# PCB.net
KiCad netlist of a schematic drawn in Altium Designer
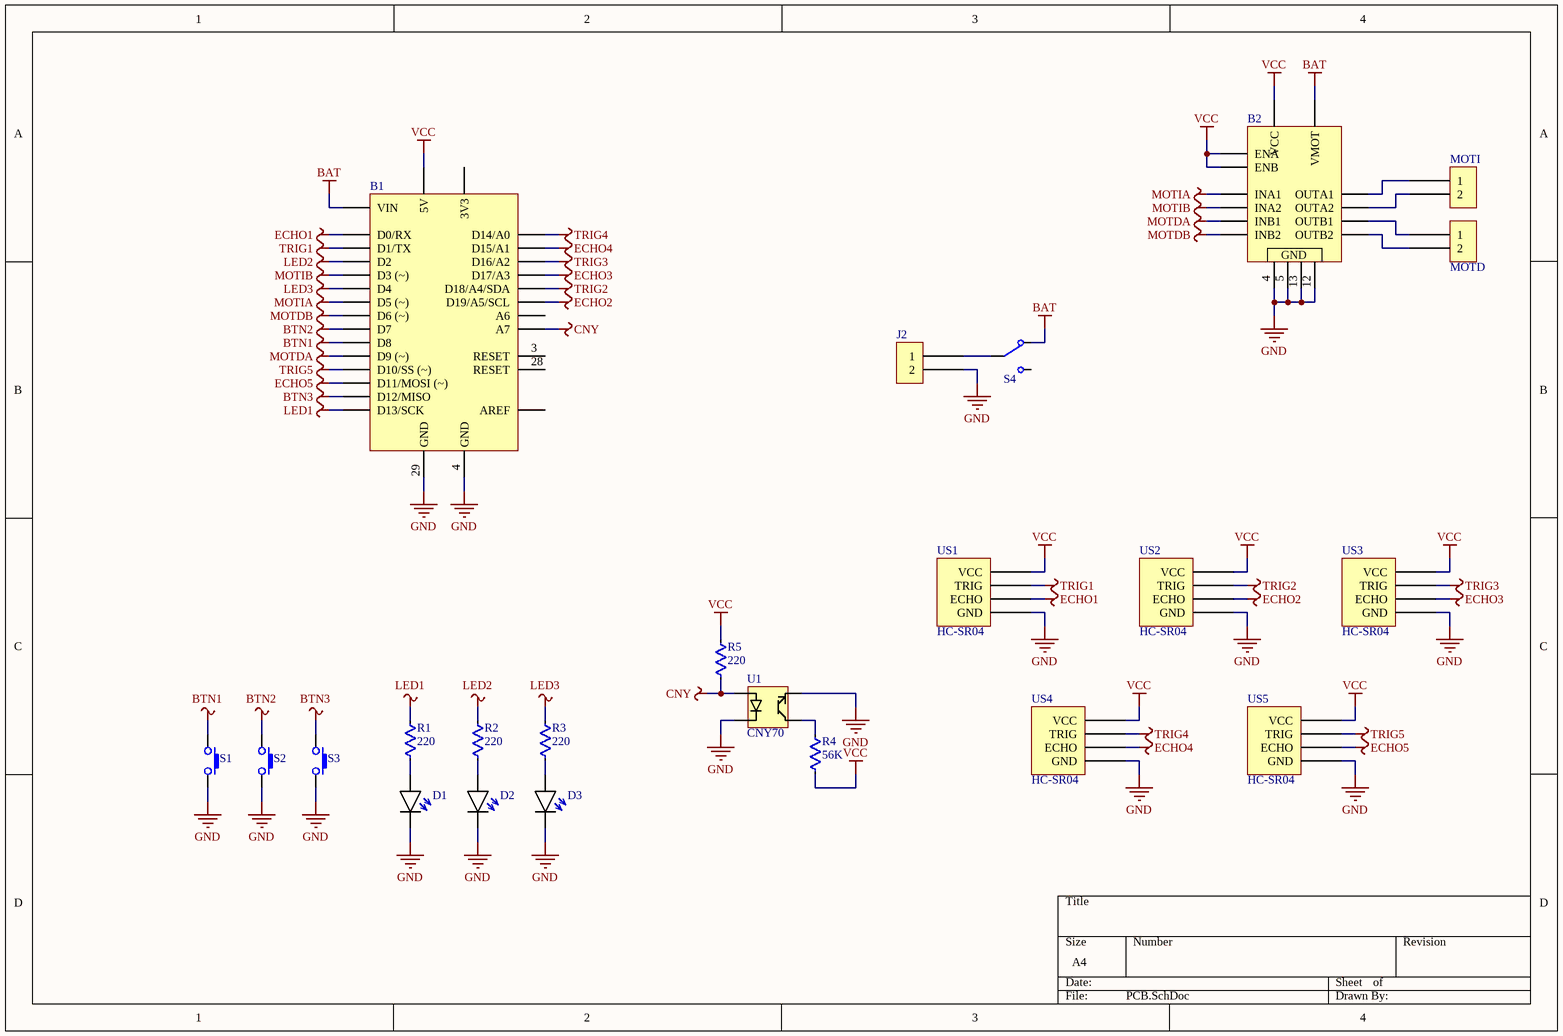
[diagram p0: PCB.SchDoc]

(export (version "E")
  (design (tool "Eeschema 10.0.6"))
  (components
    (comp (ref "B1")
      (value "ARDUINO NANO")
      (footprint "ARDUINO NANO")
      (fields (field (name "MANUFACTURER_PART_NUMBER") "Nano") (field (name "RS PART NUMBER") "6961667"))
      (libsource (lib "AltiumLibrary") (part "ARDUINO NANO"))
    )
    (comp (ref "B2") (value "L293D") (footprint "DIP16") (libsource (lib "AltiumLibrary") (part "L293D")))
    (comp (ref "D1") (value "LED") (footprint "LED-3MM-RED") (libsource (lib "AltiumLibrary") (part "LED")))
    (comp (ref "D2")
      (value "LED")
      (footprint "LED-3MM-YELLOW")
      (libsource (lib "AltiumLibrary") (part "LED"))
    )
    (comp (ref "D3") (value "LED") (footprint "LED-3MM-GREEN") (libsource (lib "AltiumLibrary") (part "LED")))
    (comp (ref "J2") (value "Header 1x2") (footprint "HEADER 1x2") (libsource (lib "") (part "Header 1x2_1")))
    (comp (ref "MOTD")
      (value "Header 1x2")
      (footprint "HEADER 1x2")
      (libsource (lib "AltiumLibrary") (part "Header 1x2"))
    )
    (comp (ref "MOTI")
      (value "Header 1x2")
      (footprint "HEADER 1x2")
      (libsource (lib "AltiumLibrary") (part "Header 1x2"))
    )
    (comp (ref "R1")
      (value "220")
      (footprint "RES VERTICAL")
      (fields (field (name "Comment") "RES"))
      (libsource (lib "AltiumLibrary") (part "RES"))
    )
    (comp (ref "R2")
      (value "220")
      (footprint "RES-Axial-400mil")
      (fields (field (name "Comment") "RES"))
      (libsource (lib "AltiumLibrary") (part "RES"))
    )
    (comp (ref "R3")
      (value "220")
      (footprint "RES-Axial-400mil")
      (fields (field (name "Comment") "RES"))
      (libsource (lib "AltiumLibrary") (part "RES"))
    )
    (comp (ref "R4")
      (value "56K")
      (footprint "RES-Axial-400mil")
      (fields (field (name "Comment") "RES"))
      (libsource (lib "AltiumLibrary") (part "RES"))
    )
    (comp (ref "R5")
      (value "220")
      (footprint "RES-Axial-400mil")
      (fields (field (name "Comment") "RES"))
      (libsource (lib "AltiumLibrary") (part "RES"))
    )
    (comp (ref "S1")
      (value "BUTTON")
      (footprint "TACT_SWITCH-SMALL-4PIN")
      (libsource (lib "AltiumLibrary") (part "BUTTON"))
    )
    (comp (ref "S2")
      (value "BUTTON")
      (footprint "TACT_SWITCH-SMALL-4PIN")
      (libsource (lib "AltiumLibrary") (part "BUTTON"))
    )
    (comp (ref "S3")
      (value "BUTTON")
      (footprint "TACT_SWITCH-SMALL-4PIN")
      (libsource (lib "AltiumLibrary") (part "BUTTON"))
    )
    (comp (ref "S4")
      (value "SLIDE-SWITCH")
      (footprint "SWITCH")
      (libsource (lib "AltiumLibrary") (part "SLIDE-SWITCH"))
    )
    (comp (ref "U1") (value "CNY70") (footprint "CNY70") (libsource (lib "AltiumLibrary") (part "CNY70")))
    (comp (ref "US1")
      (value "HC-SR04")
      (footprint "HC-SR04")
      (libsource (lib "AltiumLibrary") (part "HC-SR04"))
    )
    (comp (ref "US2")
      (value "HC-SR04")
      (footprint "HC-SR04")
      (libsource (lib "AltiumLibrary") (part "HC-SR04"))
    )
    (comp (ref "US3")
      (value "HC-SR04")
      (footprint "HC-SR04")
      (libsource (lib "AltiumLibrary") (part "HC-SR04"))
    )
    (comp (ref "US4")
      (value "HC-SR04")
      (footprint "HC-SR04")
      (libsource (lib "AltiumLibrary") (part "HC-SR04"))
    )
    (comp (ref "US5")
      (value "HC-SR04")
      (footprint "HC-SR04")
      (libsource (lib "AltiumLibrary") (part "HC-SR04"))
    )
  )
  (nets
    (net (code "1") (name "BAT") (class "Default")
      (node (ref "B1") (pin "30") (pinfunction "VIN_30") (pintype "passive"))
      (node (ref "B2") (pin "8") (pinfunction "VMOT_8") (pintype "passive"))
      (node (ref "S4") (pin "1") (pintype "power_in"))
    )
    (net (code "2") (name "BTN1") (class "Default")
      (node (ref "B1") (pin "11") (pinfunction "D8_11") (pintype "passive"))
      (node (ref "S1") (pin "1") (pintype "passive"))
    )
    (net (code "3") (name "BTN2") (class "Default")
      (node (ref "B1") (pin "10") (pinfunction "D7_10") (pintype "passive"))
      (node (ref "S2") (pin "1") (pintype "passive"))
    )
    (net (code "4") (name "BTN3") (class "Default")
      (node (ref "B1") (pin "15") (pinfunction "D12/MISO_15") (pintype "passive"))
      (node (ref "S3") (pin "1") (pintype "passive"))
    )
    (net (code "5") (name "CNY") (class "Default")
      (node (ref "B1") (pin "26") (pinfunction "A7_26") (pintype "passive"))
      (node (ref "R5") (pin "1") (pintype "passive"))
      (node (ref "U1") (pin "A") (pinfunction "A_A") (pintype "passive"))
    )
    (net (code "6") (name "ECHO1") (class "Default")
      (node (ref "B1") (pin "2") (pinfunction "D0/RX_2") (pintype "passive"))
      (node (ref "US1") (pin "3") (pinfunction "ECHO_3") (pintype "passive"))
    )
    (net (code "7") (name "ECHO2") (class "Default")
      (node (ref "B1") (pin "24") (pinfunction "D19/A5/SCL_24") (pintype "passive"))
      (node (ref "US2") (pin "3") (pinfunction "ECHO_3") (pintype "passive"))
    )
    (net (code "8") (name "ECHO3") (class "Default")
      (node (ref "B1") (pin "22") (pinfunction "D17/A3_22") (pintype "passive"))
      (node (ref "US3") (pin "3") (pinfunction "ECHO_3") (pintype "passive"))
    )
    (net (code "9") (name "ECHO4") (class "Default")
      (node (ref "B1") (pin "20") (pinfunction "D15/A1_20") (pintype "passive"))
      (node (ref "US4") (pin "3") (pinfunction "ECHO_3") (pintype "passive"))
    )
    (net (code "10") (name "ECHO5") (class "Default")
      (node (ref "B1") (pin "14") (pinfunction "D11/MOSI_(~)_14") (pintype "passive"))
      (node (ref "US5") (pin "3") (pinfunction "ECHO_3") (pintype "passive"))
    )
    (net (code "11") (name "GND") (class "Default")
      (node (ref "B1") (pin "29") (pinfunction "GND_29") (pintype "passive"))
      (node (ref "B1") (pin "4") (pinfunction "GND_4") (pintype "passive"))
      (node (ref "B2") (pin "12") (pintype "passive"))
      (node (ref "B2") (pin "13") (pintype "passive"))
      (node (ref "B2") (pin "4") (pintype "passive"))
      (node (ref "B2") (pin "5") (pintype "passive"))
      (node (ref "D1") (pin "K") (pintype "passive"))
      (node (ref "D2") (pin "K") (pintype "passive"))
      (node (ref "D3") (pin "K") (pintype "passive"))
      (node (ref "J2") (pin "2") (pinfunction "2_2") (pintype "passive"))
      (node (ref "S1") (pin "2") (pintype "passive"))
      (node (ref "S2") (pin "2") (pintype "passive"))
      (node (ref "S3") (pin "2") (pintype "passive"))
      (node (ref "U1") (pin "E") (pinfunction "7.5_E") (pintype "passive"))
      (node (ref "U1") (pin "K") (pinfunction "K_K") (pintype "passive"))
      (node (ref "US1") (pin "4") (pinfunction "GND_4") (pintype "passive"))
      (node (ref "US2") (pin "4") (pinfunction "GND_4") (pintype "passive"))
      (node (ref "US3") (pin "4") (pinfunction "GND_4") (pintype "passive"))
      (node (ref "US4") (pin "4") (pinfunction "GND_4") (pintype "passive"))
      (node (ref "US5") (pin "4") (pinfunction "GND_4") (pintype "passive"))
    )
    (net (code "12") (name "LED1") (class "Default")
      (node (ref "B1") (pin "16") (pinfunction "D13/SCK_16") (pintype "passive"))
      (node (ref "R1") (pin "2") (pintype "passive"))
    )
    (net (code "13") (name "LED2") (class "Default")
      (node (ref "B1") (pin "5") (pinfunction "D2_5") (pintype "passive"))
      (node (ref "R2") (pin "2") (pintype "passive"))
    )
    (net (code "14") (name "LED3") (class "Default")
      (node (ref "B1") (pin "7") (pinfunction "D4_7") (pintype "passive"))
      (node (ref "R3") (pin "2") (pintype "passive"))
    )
    (net (code "15") (name "MOTDA") (class "Default")
      (node (ref "B1") (pin "12") (pinfunction "D9_(~)_12") (pintype "passive"))
      (node (ref "B2") (pin "10") (pinfunction "INB1_10") (pintype "passive"))
    )
    (net (code "16") (name "MOTDB") (class "Default")
      (node (ref "B1") (pin "9") (pinfunction "D6_(~)_9") (pintype "passive"))
      (node (ref "B2") (pin "15") (pinfunction "INB2_15") (pintype "passive"))
    )
    (net (code "17") (name "MOTIA") (class "Default")
      (node (ref "B1") (pin "8") (pinfunction "D5_(~)_8") (pintype "passive"))
      (node (ref "B2") (pin "2") (pinfunction "INA1_2") (pintype "passive"))
    )
    (net (code "18") (name "MOTIB") (class "Default")
      (node (ref "B1") (pin "6") (pinfunction "D3_(~)_6") (pintype "passive"))
      (node (ref "B2") (pin "7") (pinfunction "INA2_7") (pintype "passive"))
    )
    (net (code "19") (name "Net-(B2-OUTA1)") (class "Default")
      (node (ref "B2") (pin "3") (pinfunction "OUTA1_3") (pintype "passive"))
      (node (ref "MOTI") (pin "1") (pinfunction "1_1") (pintype "passive"))
    )
    (net (code "20") (name "Net-(B2-OUTA2)") (class "Default")
      (node (ref "B2") (pin "6") (pinfunction "OUTA2_6") (pintype "passive"))
      (node (ref "MOTI") (pin "2") (pinfunction "2_2") (pintype "passive"))
    )
    (net (code "21") (name "Net-(B2-OUTB1)") (class "Default")
      (node (ref "B2") (pin "11") (pinfunction "OUTB1_11") (pintype "passive"))
      (node (ref "MOTD") (pin "1") (pinfunction "1_1") (pintype "passive"))
    )
    (net (code "22") (name "Net-(B2-OUTB2)") (class "Default")
      (node (ref "B2") (pin "14") (pinfunction "OUTB2_14") (pintype "passive"))
      (node (ref "MOTD") (pin "2") (pinfunction "2_2") (pintype "passive"))
    )
    (net (code "23") (name "Net-(D1-PadA)") (class "Default")
      (node (ref "D1") (pin "A") (pintype "passive"))
      (node (ref "R1") (pin "1") (pintype "passive"))
    )
    (net (code "24") (name "Net-(D2-PadA)") (class "Default")
      (node (ref "D2") (pin "A") (pintype "passive"))
      (node (ref "R2") (pin "1") (pintype "passive"))
    )
    (net (code "25") (name "Net-(D3-PadA)") (class "Default")
      (node (ref "D3") (pin "A") (pintype "passive"))
      (node (ref "R3") (pin "1") (pintype "passive"))
    )
    (net (code "26") (name "Net-(J2-Pad1)") (class "Default")
      (node (ref "J2") (pin "1") (pinfunction "1_1") (pintype "passive"))
      (node (ref "S4") (pin "2") (pintype "power_in"))
    )
    (net (code "27") (name "Net-(R4-Pad2)") (class "Default")
      (node (ref "R4") (pin "2") (pintype "passive"))
      (node (ref "U1") (pin "C") (pinfunction "C_C") (pintype "passive"))
    )
    (net (code "28") (name "TRIG1") (class "Default")
      (node (ref "B1") (pin "1") (pinfunction "D1/TX_1") (pintype "passive"))
      (node (ref "US1") (pin "2") (pinfunction "TRIG_2") (pintype "passive"))
    )
    (net (code "29") (name "TRIG2") (class "Default")
      (node (ref "B1") (pin "23") (pinfunction "D18/A4/SDA_23") (pintype "passive"))
      (node (ref "US2") (pin "2") (pinfunction "TRIG_2") (pintype "passive"))
    )
    (net (code "30") (name "TRIG3") (class "Default")
      (node (ref "B1") (pin "21") (pinfunction "D16/A2_21") (pintype "passive"))
      (node (ref "US3") (pin "2") (pinfunction "TRIG_2") (pintype "passive"))
    )
    (net (code "31") (name "TRIG4") (class "Default")
      (node (ref "B1") (pin "19") (pinfunction "D14/A0_19") (pintype "passive"))
      (node (ref "US4") (pin "2") (pinfunction "TRIG_2") (pintype "passive"))
    )
    (net (code "32") (name "TRIG5") (class "Default")
      (node (ref "B1") (pin "13") (pinfunction "D10/SS_(~)_13") (pintype "passive"))
      (node (ref "US5") (pin "2") (pinfunction "TRIG_2") (pintype "passive"))
    )
    (net (code "33") (name "VCC") (class "Default")
      (node (ref "B1") (pin "27") (pinfunction "5V_27") (pintype "passive"))
      (node (ref "B2") (pin "1") (pinfunction "ENA_1") (pintype "passive"))
      (node (ref "B2") (pin "16") (pinfunction "VCC_16") (pintype "passive"))
      (node (ref "B2") (pin "9") (pinfunction "ENB_9") (pintype "passive"))
      (node (ref "R4") (pin "1") (pintype "passive"))
      (node (ref "R5") (pin "2") (pintype "passive"))
      (node (ref "US1") (pin "1") (pinfunction "VCC_1") (pintype "passive"))
      (node (ref "US2") (pin "1") (pinfunction "VCC_1") (pintype "passive"))
      (node (ref "US3") (pin "1") (pinfunction "VCC_1") (pintype "passive"))
      (node (ref "US4") (pin "1") (pinfunction "VCC_1") (pintype "passive"))
      (node (ref "US5") (pin "1") (pinfunction "VCC_1") (pintype "passive"))
    )
    (net (code "34") (name "unconnected-(B1-3V3-Pad17)") (class "Default")
      (node (ref "B1") (pin "17") (pinfunction "3V3_17") (pintype "passive"))
    )
    (net (code "35") (name "unconnected-(B1-A6-Pad25)") (class "Default")
      (node (ref "B1") (pin "25") (pinfunction "A6_25") (pintype "passive"))
    )
    (net (code "36") (name "unconnected-(B1-AREF-Pad18)") (class "Default")
      (node (ref "B1") (pin "18") (pinfunction "AREF_18") (pintype "passive"))
    )
    (net (code "37") (name "unconnected-(B1-RESET-Pad3)") (class "Default")
      (node (ref "B1") (pin "3") (pinfunction "RESET_3") (pintype "passive"))
    )
    (net (code "38") (name "unconnected-(B1-RESET-Pad28)") (class "Default")
      (node (ref "B1") (pin "28") (pinfunction "RESET_28") (pintype "passive"))
    )
    (net (code "39") (name "unconnected-(S4-Pad3)") (class "Default")
      (node (ref "S4") (pin "3") (pintype "power_in"))
    )
  )
)
